# Sequencer_RevC.net
KiCad netlist of a schematic drawn in EAGLE
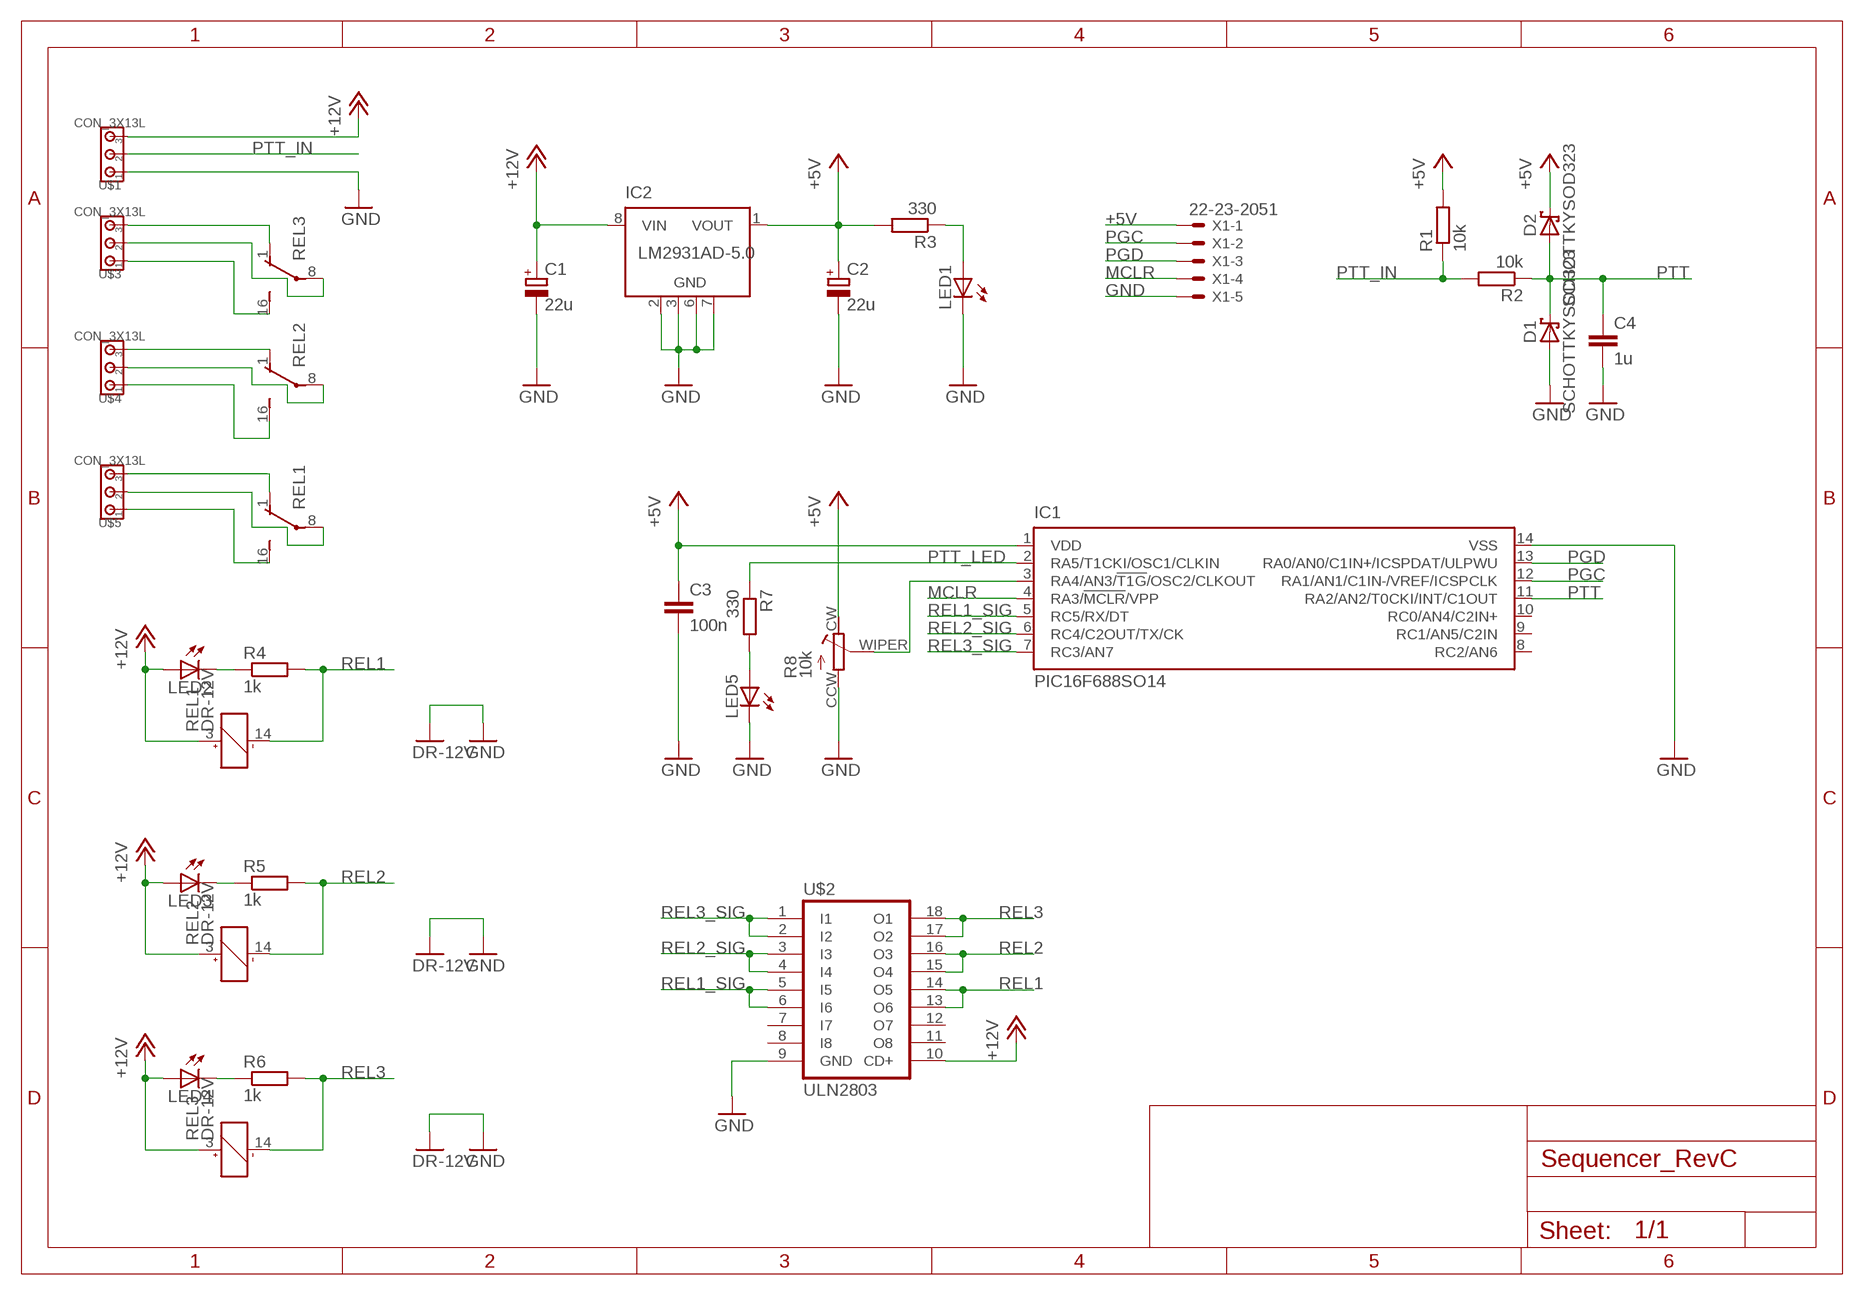
[diagram p0: schematic, sheet 1]

(export (version "E")
  (design (tool "Eeschema 10.0.6"))
  (components
    (comp (ref "C1")
      (value "22u")
      (footprint "eagle-import:SMC_C")
      (libsource (lib "eagle-import") (part "C_POLARIZEDSMC_C"))
    )
    (comp (ref "C2")
      (value "22u")
      (footprint "eagle-import:SMC_C")
      (libsource (lib "eagle-import") (part "C_POLARIZEDSMC_C"))
    )
    (comp (ref "C3")
      (value "100n")
      (footprint "eagle-import:C0805")
      (libsource (lib "eagle-import") (part "CC0805"))
    )
    (comp (ref "C4")
      (value "1u")
      (footprint "eagle-import:C0805")
      (libsource (lib "eagle-import") (part "CC0805"))
    )
    (comp (ref "D1")
      (value "SCHOTTKYSOD323")
      (footprint "eagle-import:SOD323")
      (libsource (lib "eagle-import") (part "SCHOTTKYSOD323"))
    )
    (comp (ref "D2")
      (value "SCHOTTKYSOD323")
      (footprint "eagle-import:SOD323")
      (libsource (lib "eagle-import") (part "SCHOTTKYSOD323"))
    )
    (comp (ref "IC1")
      (value "PIC16F688SO14")
      (footprint "eagle-import:SO14")
      (libsource (lib "eagle-import") (part "PIC16F688SO14"))
    )
    (comp (ref "IC2")
      (value "LM2931AD-5.0")
      (footprint "eagle-import:SO8")
      (libsource (lib "eagle-import") (part "LM2931AD-5.0"))
    )
    (comp (ref "LED1")
      (value "LED0805")
      (footprint "eagle-import:LED0805")
      (libsource (lib "eagle-import") (part "LED0805"))
    )
    (comp (ref "LED2")
      (value "LED0805")
      (footprint "eagle-import:LED0805")
      (libsource (lib "eagle-import") (part "LED0805"))
    )
    (comp (ref "LED3")
      (value "LED0805")
      (footprint "eagle-import:LED0805")
      (libsource (lib "eagle-import") (part "LED0805"))
    )
    (comp (ref "LED4")
      (value "LED0805")
      (footprint "eagle-import:LED0805")
      (libsource (lib "eagle-import") (part "LED0805"))
    )
    (comp (ref "LED5")
      (value "LED0805")
      (footprint "eagle-import:LED0805")
      (libsource (lib "eagle-import") (part "LED0805"))
    )
    (comp (ref "R1")
      (value "10k")
      (footprint "eagle-import:R0805")
      (libsource (lib "eagle-import") (part "RESISTORR0805"))
    )
    (comp (ref "R2")
      (value "10k")
      (footprint "eagle-import:R0805")
      (libsource (lib "eagle-import") (part "RESISTORR0805"))
    )
    (comp (ref "R3")
      (value "330")
      (footprint "eagle-import:R0805")
      (libsource (lib "eagle-import") (part "RESISTORR0805"))
    )
    (comp (ref "R4")
      (value "1k")
      (footprint "eagle-import:R0805")
      (libsource (lib "eagle-import") (part "RESISTORR0805"))
    )
    (comp (ref "R5")
      (value "1k")
      (footprint "eagle-import:R0805")
      (libsource (lib "eagle-import") (part "RESISTORR0805"))
    )
    (comp (ref "R6")
      (value "1k")
      (footprint "eagle-import:R0805")
      (libsource (lib "eagle-import") (part "RESISTORR0805"))
    )
    (comp (ref "R7")
      (value "330")
      (footprint "eagle-import:R0805")
      (libsource (lib "eagle-import") (part "RESISTORR0805"))
    )
    (comp (ref "R8")
      (value "10k")
      (footprint "eagle-import:RTRIM3314G")
      (libsource (lib "eagle-import") (part "TRIMMER3314G"))
    )
    (comp (ref "REL1")
      (value "DR-12V")
      (footprint "eagle-import:DR-12V")
      (libsource (lib "eagle-import") (part "DR-12V"))
    )
    (comp (ref "REL2")
      (value "DR-12V")
      (footprint "eagle-import:DR-12V")
      (libsource (lib "eagle-import") (part "DR-12V"))
    )
    (comp (ref "REL3")
      (value "DR-12V")
      (footprint "eagle-import:DR-12V")
      (libsource (lib "eagle-import") (part "DR-12V"))
    )
    (comp (ref "U$1")
      (value "CON_3X13L")
      (footprint "eagle-import:200MIL_3X")
      (libsource (lib "eagle-import") (part "CON_3X13L"))
    )
    (comp (ref "U$2")
      (value "ULN2803")
      (footprint "eagle-import:SO18W")
      (libsource (lib "eagle-import") (part "ULN2803"))
    )
    (comp (ref "U$3")
      (value "CON_3X13L")
      (footprint "eagle-import:200MIL_3X")
      (libsource (lib "eagle-import") (part "CON_3X13L"))
    )
    (comp (ref "U$4")
      (value "CON_3X13L")
      (footprint "eagle-import:200MIL_3X")
      (libsource (lib "eagle-import") (part "CON_3X13L"))
    )
    (comp (ref "U$5")
      (value "CON_3X13L")
      (footprint "eagle-import:200MIL_3X")
      (libsource (lib "eagle-import") (part "CON_3X13L"))
    )
    (comp (ref "X1")
      (value "22-23-2051")
      (footprint "eagle-import:22-23-2051")
      (fields (field (name "MF") "MOLEX"))
      (libsource (lib "eagle-import") (part "22-23-2051"))
    )
  )
  (nets
    (net (code "1") (name "+5V") (class "Default")
      (node (ref "C2") (pin "+") (pinfunction "+_+") (pintype "passive"))
      (node (ref "C3") (pin "1") (pinfunction "1_1") (pintype "passive"))
      (node (ref "D2") (pin "C") (pinfunction "C_C") (pintype "passive"))
      (node (ref "IC1") (pin "1") (pinfunction "VDD_1") (pintype "power_in"))
      (node (ref "IC2") (pin "1") (pinfunction "VOUT_1") (pintype "output"))
      (node (ref "R1") (pin "2") (pinfunction "2_2") (pintype "passive"))
      (node (ref "R3") (pin "2") (pinfunction "2_2") (pintype "passive"))
      (node (ref "R8") (pin "CW") (pinfunction "CW_CW") (pintype "passive"))
      (node (ref "X1") (pin "1") (pinfunction "S_1") (pintype "passive"))
    )
    (net (code "2") (name "+12V") (class "Default")
      (node (ref "C1") (pin "+") (pinfunction "+_+") (pintype "passive"))
      (node (ref "IC2") (pin "8") (pinfunction "VIN_8") (pintype "passive"))
      (node (ref "LED2") (pin "A") (pinfunction "A_A") (pintype "passive"))
      (node (ref "LED3") (pin "A") (pinfunction "A_A") (pintype "passive"))
      (node (ref "LED4") (pin "A") (pinfunction "A_A") (pintype "passive"))
      (node (ref "REL1") (pin "3") (pinfunction "+_3") (pintype "passive"))
      (node (ref "REL2") (pin "3") (pinfunction "+_3") (pintype "passive"))
      (node (ref "REL3") (pin "3") (pinfunction "+_3") (pintype "passive"))
      (node (ref "U$1") (pin "3") (pinfunction "3_3") (pintype "passive"))
      (node (ref "U$2") (pin "10") (pinfunction "CD+_10") (pintype "passive"))
    )
    (net (code "3") (name "/MCLR") (class "Default")
      (node (ref "IC1") (pin "4") (pinfunction "RA3/~{MCLR}/VPP_4") (pintype "bidirectional"))
      (node (ref "X1") (pin "4") (pinfunction "S_4") (pintype "passive"))
    )
    (net (code "4") (name "/PGC") (class "Default")
      (node (ref "IC1") (pin "12") (pinfunction "RA1/AN1/C1IN-/VREF/ICSPCLK_12") (pintype "bidirectional"))
      (node (ref "X1") (pin "2") (pinfunction "S_2") (pintype "passive"))
    )
    (net (code "5") (name "/PGD") (class "Default")
      (node (ref "IC1") (pin "13") (pinfunction "RA0/AN0/C1IN+/ICSPDAT/ULPWU_13") (pintype "bidirectional"))
      (node (ref "X1") (pin "3") (pinfunction "S_3") (pintype "passive"))
    )
    (net (code "6") (name "/PTT") (class "Default")
      (node (ref "C4") (pin "1") (pinfunction "1_1") (pintype "passive"))
      (node (ref "D1") (pin "C") (pinfunction "C_C") (pintype "passive"))
      (node (ref "D2") (pin "A") (pinfunction "A_A") (pintype "passive"))
      (node (ref "IC1") (pin "11") (pinfunction "RA2/AN2/T0CKI/INT/C1OUT_11") (pintype "bidirectional"))
      (node (ref "R2") (pin "1") (pinfunction "1_1") (pintype "passive"))
    )
    (net (code "7") (name "/PTT_IN") (class "Default")
      (node (ref "R1") (pin "1") (pinfunction "1_1") (pintype "passive"))
      (node (ref "R2") (pin "2") (pinfunction "2_2") (pintype "passive"))
      (node (ref "U$1") (pin "2") (pinfunction "2_2") (pintype "passive"))
    )
    (net (code "8") (name "/PTT_LED") (class "Default")
      (node (ref "IC1") (pin "2") (pinfunction "RA5/T1CKI/OSC1/CLKIN_2") (pintype "input"))
      (node (ref "R7") (pin "1") (pinfunction "1_1") (pintype "passive"))
    )
    (net (code "9") (name "/REL1") (class "Default")
      (node (ref "R4") (pin "2") (pinfunction "2_2") (pintype "passive"))
      (node (ref "REL1") (pin "14") (pinfunction "-_14") (pintype "passive"))
      (node (ref "U$2") (pin "13") (pinfunction "O6_13") (pintype "open_collector"))
      (node (ref "U$2") (pin "14") (pinfunction "O5_14") (pintype "open_collector"))
    )
    (net (code "10") (name "/REL1_SIG") (class "Default")
      (node (ref "IC1") (pin "5") (pinfunction "RC5/RX/DT_5") (pintype "bidirectional"))
      (node (ref "U$2") (pin "5") (pinfunction "I5_5") (pintype "input"))
      (node (ref "U$2") (pin "6") (pinfunction "I6_6") (pintype "input"))
    )
    (net (code "11") (name "/REL2") (class "Default")
      (node (ref "R5") (pin "2") (pinfunction "2_2") (pintype "passive"))
      (node (ref "REL2") (pin "14") (pinfunction "-_14") (pintype "passive"))
      (node (ref "U$2") (pin "15") (pinfunction "O4_15") (pintype "open_collector"))
      (node (ref "U$2") (pin "16") (pinfunction "O3_16") (pintype "open_collector"))
    )
    (net (code "12") (name "/REL2_SIG") (class "Default")
      (node (ref "IC1") (pin "6") (pinfunction "RC4/C2OUT/TX/CK_6") (pintype "bidirectional"))
      (node (ref "U$2") (pin "3") (pinfunction "I3_3") (pintype "input"))
      (node (ref "U$2") (pin "4") (pinfunction "I4_4") (pintype "input"))
    )
    (net (code "13") (name "/REL3") (class "Default")
      (node (ref "R6") (pin "2") (pinfunction "2_2") (pintype "passive"))
      (node (ref "REL3") (pin "14") (pinfunction "-_14") (pintype "passive"))
      (node (ref "U$2") (pin "17") (pinfunction "O2_17") (pintype "open_collector"))
      (node (ref "U$2") (pin "18") (pinfunction "O1_18") (pintype "open_collector"))
    )
    (net (code "14") (name "/REL3_SIG") (class "Default")
      (node (ref "IC1") (pin "7") (pinfunction "RC3/AN7_7") (pintype "bidirectional"))
      (node (ref "U$2") (pin "1") (pinfunction "I1_1") (pintype "input"))
      (node (ref "U$2") (pin "2") (pinfunction "I2_2") (pintype "input"))
    )
    (net (code "15") (name "GND") (class "Default")
      (node (ref "C1") (pin "-") (pinfunction "-_-") (pintype "passive"))
      (node (ref "C2") (pin "-") (pinfunction "-_-") (pintype "passive"))
      (node (ref "C3") (pin "2") (pinfunction "2_2") (pintype "passive"))
      (node (ref "C4") (pin "2") (pinfunction "2_2") (pintype "passive"))
      (node (ref "D1") (pin "A") (pinfunction "A_A") (pintype "passive"))
      (node (ref "IC1") (pin "14") (pinfunction "VSS_14") (pintype "power_in"))
      (node (ref "IC2") (pin "2") (pinfunction "GND_2") (pintype "power_in"))
      (node (ref "IC2") (pin "3") (pinfunction "GND_3") (pintype "power_in"))
      (node (ref "IC2") (pin "6") (pinfunction "GND_6") (pintype "power_in"))
      (node (ref "IC2") (pin "7") (pinfunction "GND_7") (pintype "power_in"))
      (node (ref "LED1") (pin "C") (pinfunction "C_C") (pintype "passive"))
      (node (ref "LED5") (pin "C") (pinfunction "C_C") (pintype "passive"))
      (node (ref "R8") (pin "CCW") (pinfunction "CCW_CCW") (pintype "passive"))
      (node (ref "REL1") (pin "9") (pinfunction "GND_9") (pintype "power_in"))
      (node (ref "REL2") (pin "9") (pinfunction "GND_9") (pintype "power_in"))
      (node (ref "REL3") (pin "9") (pinfunction "GND_9") (pintype "power_in"))
      (node (ref "U$1") (pin "1") (pinfunction "1_1") (pintype "passive"))
      (node (ref "U$2") (pin "9") (pinfunction "GND_9") (pintype "power_in"))
      (node (ref "X1") (pin "5") (pinfunction "S_5") (pintype "passive"))
    )
    (net (code "16") (name "Net-(IC1-RA4{slash}AN3{slash}~{T1G}{slash}OSC2{slash}CLKOUT)") (class "Default")
      (node (ref "IC1") (pin "3") (pinfunction "RA4/AN3/~{T1G}/OSC2/CLKOUT_3") (pintype "bidirectional"))
      (node (ref "R8") (pin "WIPER") (pinfunction "WIPER_WIPER") (pintype "passive"))
    )
    (net (code "17") (name "Net-(LED1-PadA)") (class "Default")
      (node (ref "LED1") (pin "A") (pinfunction "A_A") (pintype "passive"))
      (node (ref "R3") (pin "1") (pinfunction "1_1") (pintype "passive"))
    )
    (net (code "18") (name "Net-(LED2-PadC)") (class "Default")
      (node (ref "LED2") (pin "C") (pinfunction "C_C") (pintype "passive"))
      (node (ref "R4") (pin "1") (pinfunction "1_1") (pintype "passive"))
    )
    (net (code "19") (name "Net-(LED3-PadC)") (class "Default")
      (node (ref "LED3") (pin "C") (pinfunction "C_C") (pintype "passive"))
      (node (ref "R5") (pin "1") (pinfunction "1_1") (pintype "passive"))
    )
    (net (code "20") (name "Net-(LED4-PadC)") (class "Default")
      (node (ref "LED4") (pin "C") (pinfunction "C_C") (pintype "passive"))
      (node (ref "R6") (pin "1") (pinfunction "1_1") (pintype "passive"))
    )
    (net (code "21") (name "Net-(LED5-PadA)") (class "Default")
      (node (ref "LED5") (pin "A") (pinfunction "A_A") (pintype "passive"))
      (node (ref "R7") (pin "2") (pinfunction "2_2") (pintype "passive"))
    )
    (net (code "22") (name "Net-(REL1B-O)") (class "Default")
      (node (ref "REL1") (pin "1") (pinfunction "O_1") (pintype "passive"))
      (node (ref "U$5") (pin "3") (pinfunction "3_3") (pintype "passive"))
    )
    (net (code "23") (name "Net-(REL1B-P)") (class "Default")
      (node (ref "REL1") (pin "8") (pinfunction "P_8") (pintype "passive"))
      (node (ref "U$5") (pin "2") (pinfunction "2_2") (pintype "passive"))
    )
    (net (code "24") (name "Net-(REL1B-S)") (class "Default")
      (node (ref "REL1") (pin "16") (pinfunction "S_16") (pintype "passive"))
      (node (ref "U$5") (pin "1") (pinfunction "1_1") (pintype "passive"))
    )
    (net (code "25") (name "Net-(REL2B-O)") (class "Default")
      (node (ref "REL2") (pin "1") (pinfunction "O_1") (pintype "passive"))
      (node (ref "U$4") (pin "3") (pinfunction "3_3") (pintype "passive"))
    )
    (net (code "26") (name "Net-(REL2B-P)") (class "Default")
      (node (ref "REL2") (pin "8") (pinfunction "P_8") (pintype "passive"))
      (node (ref "U$4") (pin "2") (pinfunction "2_2") (pintype "passive"))
    )
    (net (code "27") (name "Net-(REL2B-S)") (class "Default")
      (node (ref "REL2") (pin "16") (pinfunction "S_16") (pintype "passive"))
      (node (ref "U$4") (pin "1") (pinfunction "1_1") (pintype "passive"))
    )
    (net (code "28") (name "Net-(REL3B-O)") (class "Default")
      (node (ref "REL3") (pin "1") (pinfunction "O_1") (pintype "passive"))
      (node (ref "U$3") (pin "3") (pinfunction "3_3") (pintype "passive"))
    )
    (net (code "29") (name "Net-(REL3B-P)") (class "Default")
      (node (ref "REL3") (pin "8") (pinfunction "P_8") (pintype "passive"))
      (node (ref "U$3") (pin "2") (pinfunction "2_2") (pintype "passive"))
    )
    (net (code "30") (name "Net-(REL3B-S)") (class "Default")
      (node (ref "REL3") (pin "16") (pinfunction "S_16") (pintype "passive"))
      (node (ref "U$3") (pin "1") (pinfunction "1_1") (pintype "passive"))
    )
    (net (code "31") (name "unconnected-(IC1-RC0{slash}AN4{slash}C2IN+-Pad10)") (class "Default")
      (node (ref "IC1") (pin "10") (pinfunction "RC0/AN4/C2IN+_10") (pintype "bidirectional"))
    )
    (net (code "32") (name "unconnected-(IC1-RC1{slash}AN5{slash}C2IN-Pad9)") (class "Default")
      (node (ref "IC1") (pin "9") (pinfunction "RC1/AN5/C2IN_9") (pintype "bidirectional"))
    )
    (net (code "33") (name "unconnected-(IC1-RC2{slash}AN6-Pad8)") (class "Default")
      (node (ref "IC1") (pin "8") (pinfunction "RC2/AN6_8") (pintype "bidirectional"))
    )
    (net (code "34") (name "unconnected-(U$2-I7-Pad7)") (class "Default")
      (node (ref "U$2") (pin "7") (pinfunction "I7_7") (pintype "input"))
    )
    (net (code "35") (name "unconnected-(U$2-I8-Pad8)") (class "Default")
      (node (ref "U$2") (pin "8") (pinfunction "I8_8") (pintype "input"))
    )
    (net (code "36") (name "unconnected-(U$2-O7-Pad12)") (class "Default")
      (node (ref "U$2") (pin "12") (pinfunction "O7_12") (pintype "open_collector"))
    )
    (net (code "37") (name "unconnected-(U$2-O8-Pad11)") (class "Default")
      (node (ref "U$2") (pin "11") (pinfunction "O8_11") (pintype "open_collector"))
    )
  )
)
